# EFR32.net
KiCad netlist of a schematic drawn in Altium Designer
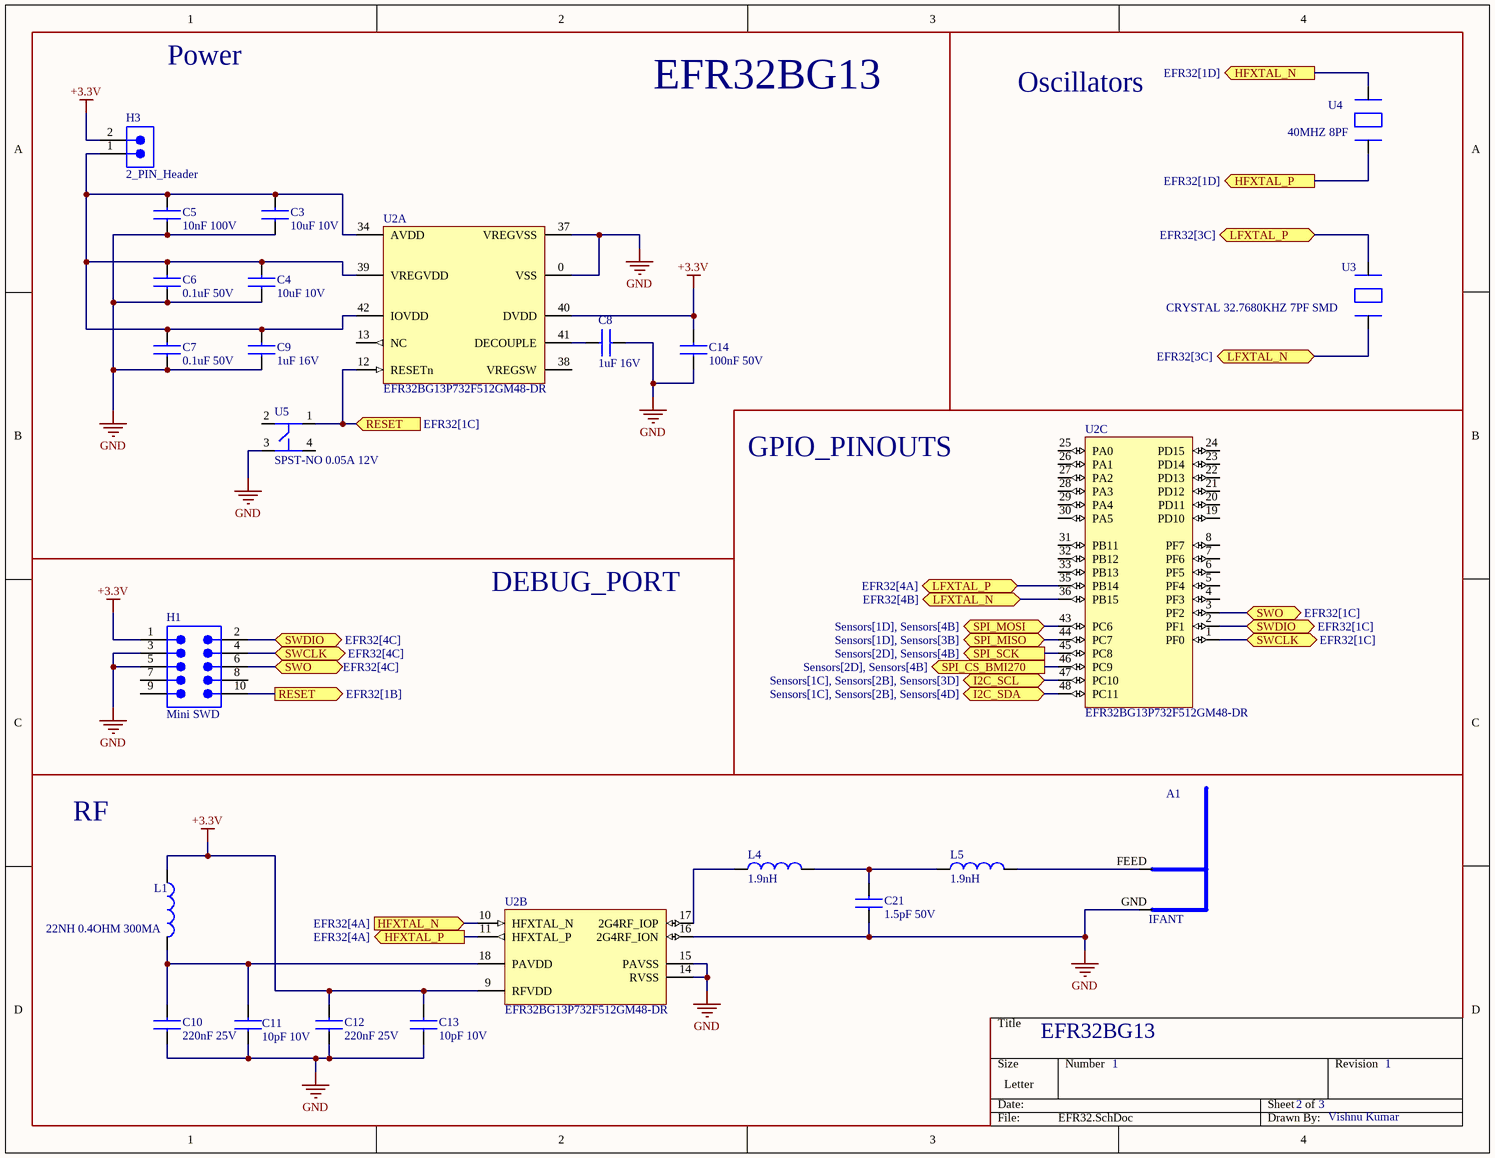
[diagram p0: EFR32.SchDoc]

(export (version "E")
  (design (tool "Eeschema 10.0.6"))
  (components
    (comp (ref "A1")
      (value "IFANT")
      (footprint "IFANT_2P4")
      (libsource (lib "LPEDT_project_library") (part "IFANT_2P4"))
    )
    (comp (ref "C3")
      (value "10uF 10V")
      (footprint "CAP_0603_1MM")
      (fields
        (field (name "MANUFACTURER") "Cal-Chip Electronics")
        (field (name "MANUFACTURER PART NUMBER") "GMC10X5R106M10NT")
      )
      (libsource (lib "LPEDT_project_library") (part "CC_10uF_10v_0603"))
    )
    (comp (ref "C4")
      (value "10uF 10V")
      (footprint "CAP_0603_1MM")
      (fields
        (field (name "MANUFACTURER") "Cal-Chip Electronics")
        (field (name "MANUFACTURER PART NUMBER") "GMC10X5R106M10NT")
      )
      (libsource (lib "LPEDT_project_library") (part "CC_10uF_10v_0603"))
    )
    (comp (ref "C5")
      (value "10nF 100V")
      (footprint "CAP_0603_1MM")
      (fields
        (field (name "MANUFACTURER") "Murata")
        (field (name "MANUFACTURER PART NUMBER") "GCM188R72A103KA37D")
      )
      (libsource (lib "LPEDT_project_library") (part "GCM188R72A103KA37D"))
    )
    (comp (ref "C6")
      (value "0.1uF 50V")
      (footprint "CAP_0603_1MM")
      (fields
        (field (name "MANUFACTURER") "Yageo")
        (field (name "MANUFACTURER PART NUMBER") "CC0603ZRY5V9BB104")
      )
      (libsource (lib "LPEDT_project_library") (part "CC_0.1uF_0603_ZRY5V9BB104"))
    )
    (comp (ref "C7")
      (value "0.1uF 50V")
      (footprint "CAP_0603_1MM")
      (fields
        (field (name "MANUFACTURER") "Yageo")
        (field (name "MANUFACTURER PART NUMBER") "CC0603ZRY5V9BB104")
      )
      (libsource (lib "LPEDT_project_library") (part "CC_0.1uF_0603_ZRY5V9BB104"))
    )
    (comp (ref "C8")
      (value "1uF 16V")
      (footprint "CAP_0603_1MM")
      (fields
        (field (name "MANUFACTURER") "Samsung")
        (field (name "MANUFACTURER PART NUMBER") "CL10A105KO8NNND")
      )
      (libsource (lib "LPEDT_project_library") (part "CC_1uF_16v_0603"))
    )
    (comp (ref "C9")
      (value "1uF 16V")
      (footprint "CAP_0603_1MM")
      (fields
        (field (name "MANUFACTURER") "Samsung")
        (field (name "MANUFACTURER PART NUMBER") "CL10A105KO8NNND")
      )
      (libsource (lib "LPEDT_project_library") (part "CC_1uF_16v_0603"))
    )
    (comp (ref "C10")
      (value "220nF 25V")
      (footprint "CAP_0603_1MM")
      (fields
        (field (name "MANUFACTURER") "Walsin Technologies")
        (field (name "MANUFACTURER PART NUMBER") "0603X224K250CT")
      )
      (libsource (lib "LPEDT_project_library") (part "CC_220nF_25V_0603"))
    )
    (comp (ref "C11")
      (value "10pF 10V")
      (footprint "CAP_0603_1MM")
      (description "10 pF ±5% 10V Ceramic Capacitor C0G, NP0 0603 (1608 Metric)")
      (libsource (lib "LPEDT_project_library") (part "CC_10pF_10V_0603"))
    )
    (comp (ref "C12")
      (value "220nF 25V")
      (footprint "CAP_0603_1MM")
      (fields
        (field (name "MANUFACTURER") "Walsin Technologies")
        (field (name "MANUFACTURER PART NUMBER") "0603X224K250CT")
      )
      (libsource (lib "LPEDT_project_library") (part "CC_220nF_25V_0603"))
    )
    (comp (ref "C13")
      (value "10pF 10V")
      (footprint "CAP_0603_1MM")
      (description "10 pF ±5% 10V Ceramic Capacitor C0G, NP0 0603 (1608 Metric)")
      (libsource (lib "LPEDT_project_library") (part "CC_10pF_10V_0603"))
    )
    (comp (ref "C14")
      (value "100nF 50V")
      (footprint "CAP_0603_1MM")
      (fields
        (field (name "MANUFACTURER") "Yageo")
        (field (name "MANUFACTURER PART NUMBER") "CC0603ZRY5V9BB104")
      )
      (libsource (lib "LPEDT_project_library") (part "CC_0.1uF_0603_ZRY5V9BB104"))
    )
    (comp (ref "C21")
      (value "1.5pF 50V")
      (footprint "CAPC1005X55N")
      (description "1.5 pF ±0.5pF 50V Ceramic Capacitor C0G, NP0 0402 (1005 Metric)")
      (fields
        (field (name "MANUFACTURER") "Wurth Electronics")
        (field (name "MANUFACTURER PART NUMBER") "885012005050")
      )
      (libsource (lib "LPEDT_project_library") (part "CC_1.5pF_885012005050"))
    )
    (comp (ref "H1")
      (value "Mini SWD")
      (footprint "FTSH-105-01-XXX-DV-K")
      (description "Mini SWD 0.05\" Pitch Connector - 10 Pin SMT Box Header")
      (fields
        (field (name "MANUFACTURER") "Adafruit Industries")
        (field (name "MANUFACTURER PART NUMBER") "4048")
      )
      (libsource (lib "LPEDT_project_library") (part "Debug Connector Mini SWD - 0.05{dblquote}"))
    )
    (comp (ref "H3")
      (value "2_PIN_Header")
      (footprint "2-PIN_MALE_HEADER_01-IN")
      (description "CONN HEADER VERT 2POS 2.54MM")
      (fields
        (field (name "MANUFACTURER") "Sullins")
        (field (name "MANUFACTURER PART NUMBER") "PRPC002SAAN-RC")
      )
      (libsource (lib "Connectors") (part "PRPC002SAAN-RC"))
    )
    (comp (ref "L1")
      (value "22NH 0.4OHM 300MA")
      (footprint "IND_0603_1MM")
      (description "22 nH Unshielded Multilayer Inductor 300 mA 400mOhm Max 0603 (1608 Metric)")
      (fields
        (field (name "MANUFACTURER") "Tai Tech")
        (field (name "MANUFACTURER PART NUMBER") "HCI1608F-22NJ-M")
      )
      (libsource (lib "LPEDT_project_library") (part "IND_22nH_0.4OHM_300MA"))
    )
    (comp (ref "L4")
      (value "1.9nH")
      (footprint "CAPC1005X55N")
      (description "General Purpose Inductor, 0.0019uH, 10.527%, 1 Element, Ceramic-Core, SMD, 0402")
      (fields
        (field (name "MANUFACTURER") "Wurth Electronics")
        (field (name "MANUFACTURER PART NUMBER") "744765019A")
      )
      (libsource (lib "LPEDT_project_library") (part "IND_1.9nH"))
    )
    (comp (ref "L5")
      (value "1.9nH")
      (footprint "CAPC1005X55N")
      (description "General Purpose Inductor, 0.0019uH, 10.527%, 1 Element, Ceramic-Core, SMD, 0402")
      (fields
        (field (name "MANUFACTURER") "Wurth Electronics")
        (field (name "MANUFACTURER PART NUMBER") "744765019A")
      )
      (libsource (lib "LPEDT_project_library") (part "IND_1.9nH"))
    )
    (comp (ref "U2")
      (value "EFR32BG13P732F512GM48-DR")
      (footprint "QFN48P700X700X90_HS-49N")
      (description "IC RF TXRX+MCU BLE 48QFN")
      (fields (field (name "MANUFACTURER") "Silicon Labs"))
      (libsource (lib "LPEDT_project_library") (part "EFR32BG13P732F512GM48-DR"))
    )
    (comp (ref "U3")
      (value "CRYSTAL 32.7680KHZ 7PF SMD")
      (footprint "Oscillator_32.768kHz_SC32S-7PF20PPM")
      (description "32.768 kHz ±20ppm Crystal 7pF 70 kOhms 2-SMD, No Lead")
      (fields
        (field (name "MANUFACTURER") "Seiko")
        (field (name "MANUFACTURER PART NUMBER") "SC32S-7PF20PPM")
      )
      (libsource (lib "LPEDT_project_library") (part "Oscillator_32.768kHz"))
    )
    (comp (ref "U4")
      (value "40MHZ 8PF")
      (footprint "OSCILLATOR_40MHz_LNCD1-40M")
      (description "40 MHz ±50ppm Crystal 8pF 50 Ohms 2-SMD, No Lead")
      (fields (field (name "MANUFACTURER") "NDK") (field (name "MANUFACTURER PART NUMBER") "LNCD1-40M"))
      (libsource (lib "LPEDT_project_library") (part "Oscillator_40MHz"))
    )
    (comp (ref "U5")
      (value "SPST-NO 0.05A 12V")
      (footprint "SPDT Switch")
      (fields
        (field (name "MANUFACTURER") "ITT C&K")
        (field (name "MANUFACTURER PART NUMBER") "PTS647SN50SMTR2LFS")
      )
      (libsource (lib "LPEDT_project_library") (part "Push_Button"))
    )
  )
  (nets
    (net (code "1") (name "+3.3V") (class "Default")
      (node (ref "C12") (pin "1") (pinfunction "1_1") (pintype "passive"))
      (node (ref "C13") (pin "2") (pinfunction "2_2") (pintype "passive"))
      (node (ref "C14") (pin "1") (pinfunction "1_1") (pintype "passive"))
      (node (ref "H1") (pin "1") (pinfunction "1_1") (pintype "passive"))
      (node (ref "H3") (pin "2") (pinfunction "2_2") (pintype "passive"))
      (node (ref "L1") (pin "1") (pinfunction "1_1") (pintype "passive"))
      (node (ref "U2") (pin "40") (pinfunction "DVDD_40") (pintype "power_in"))
      (node (ref "U2") (pin "9") (pinfunction "RFVDD_9") (pintype "power_in"))
    )
    (net (code "2") (name "/HFXTAL_N") (class "Default")
      (node (ref "U2") (pin "10") (pinfunction "HFXTAL_N_10") (pintype "input"))
      (node (ref "U4") (pin "1") (pinfunction "1_1") (pintype "passive"))
    )
    (net (code "3") (name "/HFXTAL_P") (class "Default")
      (node (ref "U2") (pin "11") (pinfunction "HFXTAL_P_11") (pintype "output"))
      (node (ref "U4") (pin "2") (pinfunction "2_2") (pintype "passive"))
    )
    (net (code "4") (name "/I2C_SCL") (class "Default")
      (node (ref "U2") (pin "47") (pinfunction "PC10_47") (pintype "bidirectional"))
    )
    (net (code "5") (name "/I2C_SDA") (class "Default")
      (node (ref "U2") (pin "48") (pinfunction "PC11_48") (pintype "bidirectional"))
    )
    (net (code "6") (name "/LFXTAL_N") (class "Default")
      (node (ref "U2") (pin "36") (pinfunction "PB15_36") (pintype "bidirectional"))
      (node (ref "U3") (pin "1") (pinfunction "1_1") (pintype "passive"))
    )
    (net (code "7") (name "/LFXTAL_P") (class "Default")
      (node (ref "U2") (pin "35") (pinfunction "PB14_35") (pintype "bidirectional"))
      (node (ref "U3") (pin "2") (pinfunction "2_2") (pintype "passive"))
    )
    (net (code "8") (name "/RESET") (class "Default")
      (node (ref "H1") (pin "10") (pinfunction "10_10") (pintype "passive"))
      (node (ref "U2") (pin "12") (pinfunction "RESETn_12") (pintype "input"))
      (node (ref "U5") (pin "1") (pinfunction "1_1") (pintype "passive"))
    )
    (net (code "9") (name "/SPI_CS_BMI270") (class "Default")
      (node (ref "U2") (pin "46") (pinfunction "PC9_46") (pintype "bidirectional"))
    )
    (net (code "10") (name "/SPI_MISO") (class "Default")
      (node (ref "U2") (pin "44") (pinfunction "PC7_44") (pintype "bidirectional"))
    )
    (net (code "11") (name "/SPI_MOSI") (class "Default")
      (node (ref "U2") (pin "43") (pinfunction "PC6_43") (pintype "bidirectional"))
    )
    (net (code "12") (name "/SPI_SCK") (class "Default")
      (node (ref "U2") (pin "45") (pinfunction "PC8_45") (pintype "bidirectional"))
    )
    (net (code "13") (name "/SWCLK") (class "Default")
      (node (ref "H1") (pin "4") (pinfunction "4_4") (pintype "passive"))
      (node (ref "U2") (pin "1") (pinfunction "PF0_1") (pintype "bidirectional"))
    )
    (net (code "14") (name "/SWDIO") (class "Default")
      (node (ref "H1") (pin "2") (pinfunction "2_2") (pintype "passive"))
      (node (ref "U2") (pin "2") (pinfunction "PF1_2") (pintype "bidirectional"))
    )
    (net (code "15") (name "/SWO") (class "Default")
      (node (ref "H1") (pin "6") (pinfunction "6_6") (pintype "passive"))
      (node (ref "U2") (pin "3") (pinfunction "PF2_3") (pintype "bidirectional"))
    )
    (net (code "16") (name "GND") (class "Default")
      (node (ref "A1") (pin "GND") (pinfunction "1_GND") (pintype "passive"))
      (node (ref "C10") (pin "2") (pinfunction "2_2") (pintype "passive"))
      (node (ref "C11") (pin "2") (pinfunction "2_2") (pintype "passive"))
      (node (ref "C12") (pin "2") (pinfunction "2_2") (pintype "passive"))
      (node (ref "C13") (pin "1") (pinfunction "1_1") (pintype "passive"))
      (node (ref "C14") (pin "2") (pinfunction "2_2") (pintype "passive"))
      (node (ref "C21") (pin "2") (pinfunction "2_2") (pintype "passive"))
      (node (ref "C3") (pin "2") (pinfunction "2_2") (pintype "passive"))
      (node (ref "C4") (pin "2") (pinfunction "2_2") (pintype "passive"))
      (node (ref "C5") (pin "1") (pinfunction "1_1") (pintype "passive"))
      (node (ref "C6") (pin "1") (pinfunction "1_1") (pintype "passive"))
      (node (ref "C7") (pin "2") (pinfunction "2_2") (pintype "passive"))
      (node (ref "C8") (pin "2") (pinfunction "2_2") (pintype "passive"))
      (node (ref "C9") (pin "2") (pinfunction "2_2") (pintype "passive"))
      (node (ref "H1") (pin "3") (pinfunction "3_3") (pintype "passive"))
      (node (ref "H1") (pin "5") (pinfunction "5_5") (pintype "passive"))
      (node (ref "U2") (pin "0") (pinfunction "VSS_0") (pintype "power_in"))
      (node (ref "U2") (pin "14") (pinfunction "RVSS_14") (pintype "power_in"))
      (node (ref "U2") (pin "15") (pinfunction "PAVSS_15") (pintype "power_in"))
      (node (ref "U2") (pin "16") (pinfunction "2G4RF_ION_16") (pintype "bidirectional"))
      (node (ref "U2") (pin "37") (pinfunction "VREGVSS_37") (pintype "power_in"))
      (node (ref "U5") (pin "3") (pinfunction "3_3") (pintype "passive"))
    )
    (net (code "17") (name "Net-(A1-0)") (class "Default")
      (node (ref "A1") (pin "FEED") (pinfunction "0_FEED") (pintype "passive"))
      (node (ref "L5") (pin "2") (pinfunction "2_2") (pintype "passive"))
    )
    (net (code "18") (name "Net-(C21-Pad1)") (class "Default")
      (node (ref "C21") (pin "1") (pinfunction "1_1") (pintype "passive"))
      (node (ref "L4") (pin "2") (pinfunction "2_2") (pintype "passive"))
      (node (ref "L5") (pin "1") (pinfunction "1_1") (pintype "passive"))
    )
    (net (code "19") (name "Net-(U2A-AVDD)") (class "Default")
      (node (ref "C3") (pin "1") (pinfunction "1_1") (pintype "passive"))
      (node (ref "C4") (pin "1") (pinfunction "1_1") (pintype "passive"))
      (node (ref "C5") (pin "2") (pinfunction "2_2") (pintype "passive"))
      (node (ref "C6") (pin "2") (pinfunction "2_2") (pintype "passive"))
      (node (ref "C7") (pin "1") (pinfunction "1_1") (pintype "passive"))
      (node (ref "C9") (pin "1") (pinfunction "1_1") (pintype "passive"))
      (node (ref "H3") (pin "1") (pinfunction "1_1") (pintype "passive"))
      (node (ref "U2") (pin "34") (pinfunction "AVDD_34") (pintype "power_in"))
      (node (ref "U2") (pin "39") (pinfunction "VREGVDD_39") (pintype "power_in"))
      (node (ref "U2") (pin "42") (pinfunction "IOVDD_42") (pintype "power_in"))
    )
    (net (code "20") (name "Net-(U2A-DECOUPLE)") (class "Default")
      (node (ref "C8") (pin "1") (pinfunction "1_1") (pintype "passive"))
      (node (ref "U2") (pin "41") (pinfunction "DECOUPLE_41") (pintype "power_in"))
    )
    (net (code "21") (name "Net-(U2B-2G4RF_IOP)") (class "Default")
      (node (ref "L4") (pin "1") (pinfunction "1_1") (pintype "passive"))
      (node (ref "U2") (pin "17") (pinfunction "2G4RF_IOP_17") (pintype "bidirectional"))
    )
    (net (code "22") (name "Net-(U2B-PAVDD)") (class "Default")
      (node (ref "C10") (pin "1") (pinfunction "1_1") (pintype "passive"))
      (node (ref "C11") (pin "1") (pinfunction "1_1") (pintype "passive"))
      (node (ref "L1") (pin "2") (pinfunction "2_2") (pintype "passive"))
      (node (ref "U2") (pin "18") (pinfunction "PAVDD_18") (pintype "power_in"))
    )
    (net (code "23") (name "unconnected-(H1-Pad7)") (class "Default")
      (node (ref "H1") (pin "7") (pinfunction "7_7") (pintype "passive"))
    )
    (net (code "24") (name "unconnected-(H1-Pad8)") (class "Default")
      (node (ref "H1") (pin "8") (pinfunction "8_8") (pintype "passive"))
    )
    (net (code "25") (name "unconnected-(H1-Pad9)") (class "Default")
      (node (ref "H1") (pin "9") (pinfunction "9_9") (pintype "passive"))
    )
    (net (code "26") (name "unconnected-(U2A-NC-Pad13)") (class "Default")
      (node (ref "U2") (pin "13") (pinfunction "NC_13") (pintype "output"))
    )
    (net (code "27") (name "unconnected-(U2A-VREGSW-Pad38)") (class "Default")
      (node (ref "U2") (pin "38") (pinfunction "VREGSW_38") (pintype "power_in"))
    )
    (net (code "28") (name "unconnected-(U2C-PA0-Pad25)") (class "Default")
      (node (ref "U2") (pin "25") (pinfunction "PA0_25") (pintype "bidirectional"))
    )
    (net (code "29") (name "unconnected-(U2C-PA1-Pad26)") (class "Default")
      (node (ref "U2") (pin "26") (pinfunction "PA1_26") (pintype "bidirectional"))
    )
    (net (code "30") (name "unconnected-(U2C-PA2-Pad27)") (class "Default")
      (node (ref "U2") (pin "27") (pinfunction "PA2_27") (pintype "bidirectional"))
    )
    (net (code "31") (name "unconnected-(U2C-PA3-Pad28)") (class "Default")
      (node (ref "U2") (pin "28") (pinfunction "PA3_28") (pintype "bidirectional"))
    )
    (net (code "32") (name "unconnected-(U2C-PA4-Pad29)") (class "Default")
      (node (ref "U2") (pin "29") (pinfunction "PA4_29") (pintype "bidirectional"))
    )
    (net (code "33") (name "unconnected-(U2C-PA5-Pad30)") (class "Default")
      (node (ref "U2") (pin "30") (pinfunction "PA5_30") (pintype "bidirectional"))
    )
    (net (code "34") (name "unconnected-(U2C-PB11-Pad31)") (class "Default")
      (node (ref "U2") (pin "31") (pinfunction "PB11_31") (pintype "bidirectional"))
    )
    (net (code "35") (name "unconnected-(U2C-PB12-Pad32)") (class "Default")
      (node (ref "U2") (pin "32") (pinfunction "PB12_32") (pintype "bidirectional"))
    )
    (net (code "36") (name "unconnected-(U2C-PB13-Pad33)") (class "Default")
      (node (ref "U2") (pin "33") (pinfunction "PB13_33") (pintype "bidirectional"))
    )
    (net (code "37") (name "unconnected-(U2C-PD10-Pad19)") (class "Default")
      (node (ref "U2") (pin "19") (pinfunction "PD10_19") (pintype "bidirectional"))
    )
    (net (code "38") (name "unconnected-(U2C-PD11-Pad20)") (class "Default")
      (node (ref "U2") (pin "20") (pinfunction "PD11_20") (pintype "bidirectional"))
    )
    (net (code "39") (name "unconnected-(U2C-PD12-Pad21)") (class "Default")
      (node (ref "U2") (pin "21") (pinfunction "PD12_21") (pintype "bidirectional"))
    )
    (net (code "40") (name "unconnected-(U2C-PD13-Pad22)") (class "Default")
      (node (ref "U2") (pin "22") (pinfunction "PD13_22") (pintype "bidirectional"))
    )
    (net (code "41") (name "unconnected-(U2C-PD14-Pad23)") (class "Default")
      (node (ref "U2") (pin "23") (pinfunction "PD14_23") (pintype "bidirectional"))
    )
    (net (code "42") (name "unconnected-(U2C-PD15-Pad24)") (class "Default")
      (node (ref "U2") (pin "24") (pinfunction "PD15_24") (pintype "bidirectional"))
    )
    (net (code "43") (name "unconnected-(U2C-PF3-Pad4)") (class "Default")
      (node (ref "U2") (pin "4") (pinfunction "PF3_4") (pintype "bidirectional"))
    )
    (net (code "44") (name "unconnected-(U2C-PF4-Pad5)") (class "Default")
      (node (ref "U2") (pin "5") (pinfunction "PF4_5") (pintype "bidirectional"))
    )
    (net (code "45") (name "unconnected-(U2C-PF5-Pad6)") (class "Default")
      (node (ref "U2") (pin "6") (pinfunction "PF5_6") (pintype "bidirectional"))
    )
    (net (code "46") (name "unconnected-(U2C-PF6-Pad7)") (class "Default")
      (node (ref "U2") (pin "7") (pinfunction "PF6_7") (pintype "bidirectional"))
    )
    (net (code "47") (name "unconnected-(U2C-PF7-Pad8)") (class "Default")
      (node (ref "U2") (pin "8") (pinfunction "PF7_8") (pintype "bidirectional"))
    )
    (net (code "48") (name "unconnected-(U5-Pad2)") (class "Default")
      (node (ref "U5") (pin "2") (pinfunction "2_2") (pintype "passive"))
    )
    (net (code "49") (name "unconnected-(U5-Pad4)") (class "Default")
      (node (ref "U5") (pin "4") (pinfunction "4_4") (pintype "passive"))
    )
  )
)
